# Shield_behuizing.net
KiCad netlist of a schematic drawn in EAGLE
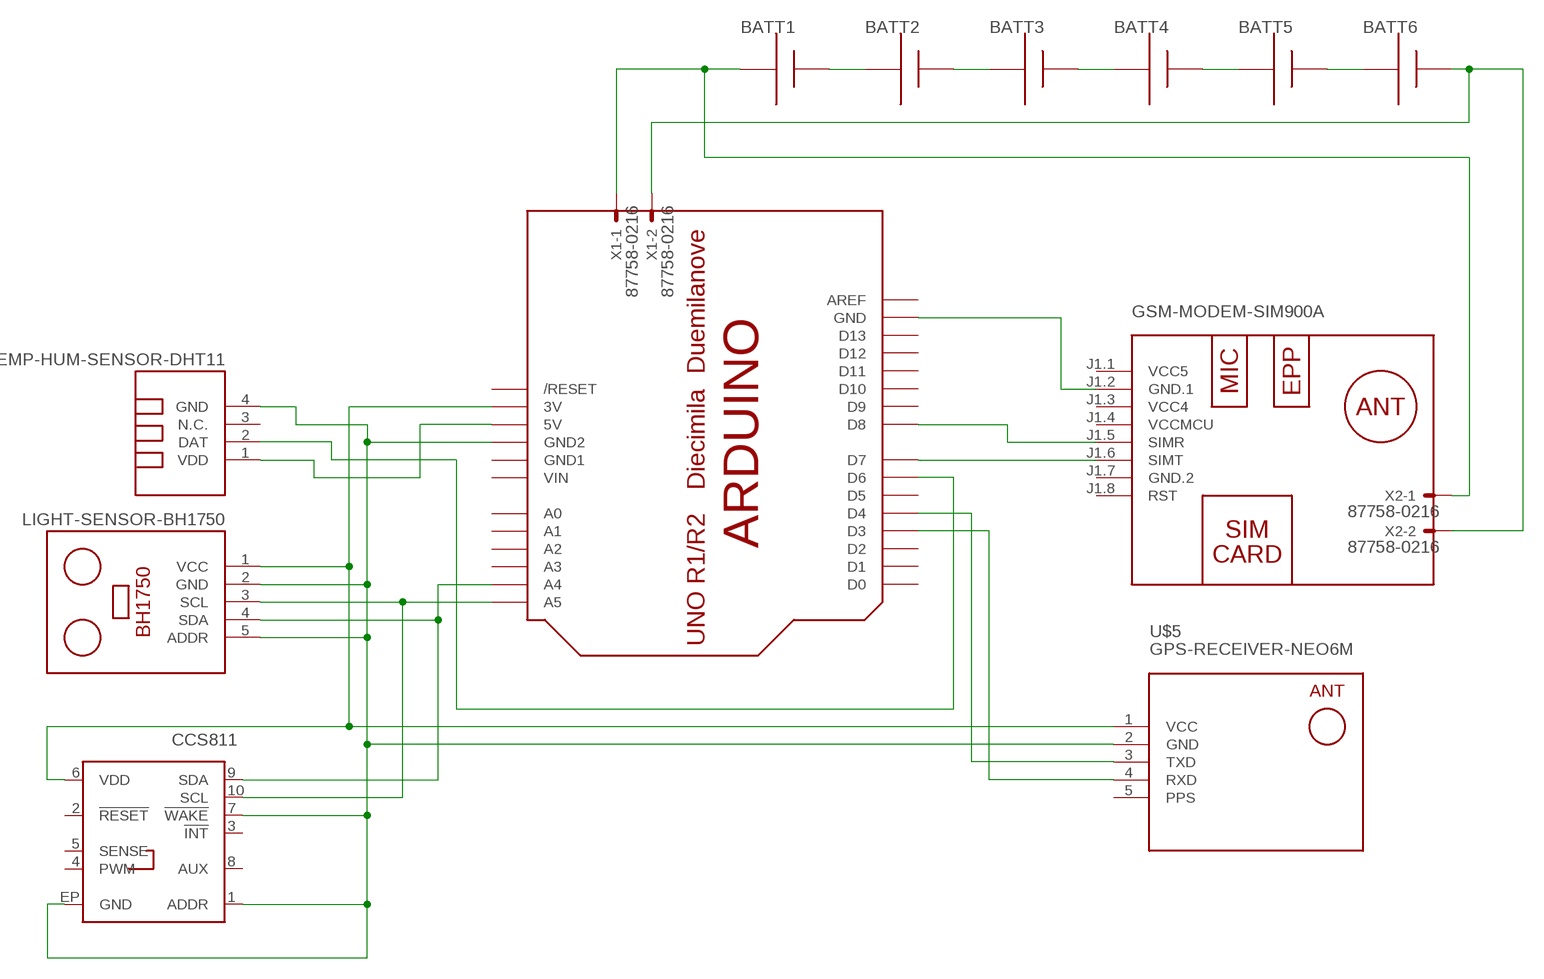
[diagram p0: schematic, sheet 1]

(export (version "E")
  (design (tool "Eeschema 10.0.6"))
  (components
    (comp (ref "BATT1")
      (value "AAA")
      (footprint "eagle-import:12BH412")
      (libsource (lib "eagle-import") (part "AAA"))
    )
    (comp (ref "BATT2")
      (value "AAA")
      (footprint "eagle-import:12BH412")
      (libsource (lib "eagle-import") (part "AAA"))
    )
    (comp (ref "BATT3")
      (value "AAA")
      (footprint "eagle-import:12BH412")
      (libsource (lib "eagle-import") (part "AAA"))
    )
    (comp (ref "BATT4")
      (value "AAA")
      (footprint "eagle-import:12BH412")
      (libsource (lib "eagle-import") (part "AAA"))
    )
    (comp (ref "BATT5")
      (value "AAA")
      (footprint "eagle-import:12BH412")
      (libsource (lib "eagle-import") (part "AAA"))
    )
    (comp (ref "BATT6")
      (value "AAA")
      (footprint "eagle-import:12BH412")
      (libsource (lib "eagle-import") (part "AAA"))
    )
    (comp (ref "U$1")
      (value "GSM-MODEM-SIM900A")
      (footprint "eagle-import:GSM-MODEM-SIM900A")
      (libsource (lib "eagle-import") (part "GSM-MODEM-SIM900A"))
    )
    (comp (ref "U$2")
      (value "ARDUINO-BPLACE")
      (footprint "eagle-import:ARDUINO-BPLACE")
      (libsource (lib "eagle-import") (part "ARDUINO-BPLACE"))
    )
    (comp (ref "U$3")
      (value "TEMP-HUM-SENSOR-DHT11")
      (footprint "eagle-import:TEMP-HUM-SENSOR-DHT11")
      (libsource (lib "eagle-import") (part "TEMP-HUM-SENSOR-DHT11"))
    )
    (comp (ref "U$4")
      (value "LIGHT-SENSOR-BH1750")
      (footprint "eagle-import:LIGHT-SENSOR-BH1750")
      (libsource (lib "eagle-import") (part "LIGHT-SENSOR-BH1750"))
    )
    (comp (ref "U$5")
      (value "GPS-RECEIVER-NEO6M")
      (footprint "eagle-import:GPS-RECEIVER-NEO6M")
      (libsource (lib "eagle-import") (part "GPS-RECEIVER-NEO6M"))
    )
    (comp (ref "U1")
      (value "CCS811")
      (footprint "eagle-import:LGA10")
      (libsource (lib "eagle-import") (part "CCS811"))
    )
    (comp (ref "X1")
      (value "87758-0216")
      (footprint "eagle-import:87758-0216")
      (fields (field (name "MF") "MOLEX"))
      (libsource (lib "eagle-import") (part "87758-0216"))
    )
    (comp (ref "X2")
      (value "87758-0216")
      (footprint "eagle-import:87758-0216")
      (fields (field (name "MF") "MOLEX"))
      (libsource (lib "eagle-import") (part "87758-0216"))
    )
  )
  (nets
    (net (code "1") (name "/GND.2") (class "Default")
      (node (ref "U$1") (pin "J1.7") (pinfunction "GND.2_J1.7") (pintype "power_in"))
    )
    (net (code "2") (name "/GND1") (class "Default")
      (node (ref "U$2") (pin "GND1") (pinfunction "GND1_GND1") (pintype "power_in"))
    )
    (net (code "3") (name "/PPS") (class "Default")
      (node (ref "U$5") (pin "5") (pinfunction "PPS_5") (pintype "power_in"))
    )
    (net (code "4") (name "/VCC4") (class "Default")
      (node (ref "U$1") (pin "J1.3") (pinfunction "VCC4_J1.3") (pintype "power_in"))
    )
    (net (code "5") (name "/VCC5") (class "Default")
      (node (ref "U$1") (pin "J1.1") (pinfunction "VCC5_J1.1") (pintype "power_in"))
    )
    (net (code "6") (name "/VCCMCU") (class "Default")
      (node (ref "U$1") (pin "J1.4") (pinfunction "VCCMCU_J1.4") (pintype "power_in"))
    )
    (net (code "7") (name "/VIN") (class "Default")
      (node (ref "U$2") (pin "VIN") (pinfunction "VIN_VIN") (pintype "power_in"))
    )
    (net (code "8") (name "Net-(BATT1-Pad+)") (class "Default")
      (node (ref "BATT1") (pin "+") (pinfunction "+_+") (pintype "bidirectional"))
      (node (ref "BATT2") (pin "-") (pinfunction "-_-") (pintype "bidirectional"))
    )
    (net (code "9") (name "Net-(BATT2-Pad+)") (class "Default")
      (node (ref "BATT2") (pin "+") (pinfunction "+_+") (pintype "bidirectional"))
      (node (ref "BATT3") (pin "-") (pinfunction "-_-") (pintype "bidirectional"))
    )
    (net (code "10") (name "Net-(BATT3-Pad+)") (class "Default")
      (node (ref "BATT3") (pin "+") (pinfunction "+_+") (pintype "bidirectional"))
      (node (ref "BATT4") (pin "-") (pinfunction "-_-") (pintype "bidirectional"))
    )
    (net (code "11") (name "Net-(BATT4-Pad+)") (class "Default")
      (node (ref "BATT4") (pin "+") (pinfunction "+_+") (pintype "bidirectional"))
      (node (ref "BATT5") (pin "-") (pinfunction "-_-") (pintype "bidirectional"))
    )
    (net (code "12") (name "Net-(BATT5-Pad+)") (class "Default")
      (node (ref "BATT5") (pin "+") (pinfunction "+_+") (pintype "bidirectional"))
      (node (ref "BATT6") (pin "-") (pinfunction "-_-") (pintype "bidirectional"))
    )
    (net (code "13") (name "Net-(U$1-GND.1)") (class "Default")
      (node (ref "U$1") (pin "J1.2") (pinfunction "GND.1_J1.2") (pintype "power_in"))
      (node (ref "U$2") (pin "GND") (pinfunction "GND_GND") (pintype "power_in"))
    )
    (net (code "14") (name "Net-(U$1-SIMR)") (class "Default")
      (node (ref "U$1") (pin "J1.5") (pinfunction "SIMR_J1.5") (pintype "bidirectional"))
      (node (ref "U$2") (pin "D8") (pinfunction "D8_D8") (pintype "bidirectional"))
    )
    (net (code "15") (name "Net-(U$1-SIMT)") (class "Default")
      (node (ref "U$1") (pin "J1.6") (pinfunction "SIMT_J1.6") (pintype "bidirectional"))
      (node (ref "U$2") (pin "D7") (pinfunction "D7_D7") (pintype "bidirectional"))
    )
    (net (code "16") (name "Net-(U$3-DAT)") (class "Default")
      (node (ref "U$2") (pin "D6") (pinfunction "D6_D6") (pintype "bidirectional"))
      (node (ref "U$3") (pin "2") (pinfunction "DAT_2") (pintype "bidirectional"))
    )
    (net (code "17") (name "Net-(U$3-GND)") (class "Default")
      (node (ref "U$2") (pin "GND2") (pinfunction "GND2_GND2") (pintype "power_in"))
      (node (ref "U$3") (pin "4") (pinfunction "GND_4") (pintype "power_in"))
      (node (ref "U$4") (pin "2") (pinfunction "GND_2") (pintype "power_in"))
      (node (ref "U$4") (pin "5") (pinfunction "ADDR_5") (pintype "bidirectional"))
      (node (ref "U$5") (pin "2") (pinfunction "GND_2") (pintype "bidirectional"))
      (node (ref "U1") (pin "1") (pinfunction "ADDR_1") (pintype "bidirectional"))
      (node (ref "U1") (pin "7") (pinfunction "~{WAKE}_7") (pintype "bidirectional"))
      (node (ref "U1") (pin "EP") (pinfunction "GND_EP") (pintype "bidirectional"))
    )
    (net (code "18") (name "Net-(U$3-VDD)") (class "Default")
      (node (ref "U$2") (pin "5V") (pinfunction "5V_5V") (pintype "power_in"))
      (node (ref "U$3") (pin "1") (pinfunction "VDD_1") (pintype "power_in"))
    )
    (net (code "19") (name "Net-(U$4-SCL)") (class "Default")
      (node (ref "U$2") (pin "A5") (pinfunction "A5_A5") (pintype "bidirectional"))
      (node (ref "U$4") (pin "3") (pinfunction "SCL_3") (pintype "bidirectional"))
      (node (ref "U1") (pin "10") (pinfunction "SCL_10") (pintype "bidirectional"))
    )
    (net (code "20") (name "Net-(U$4-SDA)") (class "Default")
      (node (ref "U$2") (pin "A4") (pinfunction "A4_A4") (pintype "bidirectional"))
      (node (ref "U$4") (pin "4") (pinfunction "SDA_4") (pintype "bidirectional"))
      (node (ref "U1") (pin "9") (pinfunction "SDA_9") (pintype "bidirectional"))
    )
    (net (code "21") (name "Net-(U$4-VCC)") (class "Default")
      (node (ref "U$2") (pin "3V") (pinfunction "3V_3V") (pintype "power_in"))
      (node (ref "U$4") (pin "1") (pinfunction "VCC_1") (pintype "power_in"))
      (node (ref "U$5") (pin "1") (pinfunction "VCC_1") (pintype "bidirectional"))
      (node (ref "U1") (pin "6") (pinfunction "VDD_6") (pintype "bidirectional"))
    )
    (net (code "22") (name "Net-(U$5-RXD)") (class "Default")
      (node (ref "U$2") (pin "D3") (pinfunction "D3_D3") (pintype "bidirectional"))
      (node (ref "U$5") (pin "4") (pinfunction "RXD_4") (pintype "power_in"))
    )
    (net (code "23") (name "Net-(U$5-TXD)") (class "Default")
      (node (ref "U$2") (pin "D4") (pinfunction "D4_D4") (pintype "bidirectional"))
      (node (ref "U$5") (pin "3") (pinfunction "TXD_3") (pintype "bidirectional"))
    )
    (net (code "24") (name "Net-(X1A-S)") (class "Default")
      (node (ref "BATT1") (pin "-") (pinfunction "-_-") (pintype "bidirectional"))
      (node (ref "X1") (pin "1") (pinfunction "S_1") (pintype "passive"))
      (node (ref "X2") (pin "1") (pinfunction "S_1") (pintype "passive"))
    )
    (net (code "25") (name "Net-(X1B-S)") (class "Default")
      (node (ref "BATT6") (pin "+") (pinfunction "+_+") (pintype "bidirectional"))
      (node (ref "X1") (pin "2") (pinfunction "S_2") (pintype "passive"))
      (node (ref "X2") (pin "2") (pinfunction "S_2") (pintype "passive"))
    )
    (net (code "26") (name "unconnected-(U$1-RST-PadJ1.8)") (class "Default")
      (node (ref "U$1") (pin "J1.8") (pinfunction "RST_J1.8") (pintype "bidirectional"))
    )
    (net (code "27") (name "unconnected-(U$2-PadA0)") (class "Default")
      (node (ref "U$2") (pin "A0") (pinfunction "A0_A0") (pintype "bidirectional"))
    )
    (net (code "28") (name "unconnected-(U$2-PadA1)") (class "Default")
      (node (ref "U$2") (pin "A1") (pinfunction "A1_A1") (pintype "bidirectional"))
    )
    (net (code "29") (name "unconnected-(U$2-PadA2)") (class "Default")
      (node (ref "U$2") (pin "A2") (pinfunction "A2_A2") (pintype "bidirectional"))
    )
    (net (code "30") (name "unconnected-(U$2-PadA3)") (class "Default")
      (node (ref "U$2") (pin "A3") (pinfunction "A3_A3") (pintype "bidirectional"))
    )
    (net (code "31") (name "unconnected-(U$2-PadAREF)") (class "Default")
      (node (ref "U$2") (pin "AREF") (pinfunction "AREF_AREF") (pintype "bidirectional"))
    )
    (net (code "32") (name "unconnected-(U$2-PadD0)") (class "Default")
      (node (ref "U$2") (pin "D0") (pinfunction "D0_D0") (pintype "bidirectional"))
    )
    (net (code "33") (name "unconnected-(U$2-PadD1)") (class "Default")
      (node (ref "U$2") (pin "D1") (pinfunction "D1_D1") (pintype "bidirectional"))
    )
    (net (code "34") (name "unconnected-(U$2-PadD2)") (class "Default")
      (node (ref "U$2") (pin "D2") (pinfunction "D2_D2") (pintype "bidirectional"))
    )
    (net (code "35") (name "unconnected-(U$2-PadD5)") (class "Default")
      (node (ref "U$2") (pin "D5") (pinfunction "D5_D5") (pintype "bidirectional"))
    )
    (net (code "36") (name "unconnected-(U$2-PadD9)") (class "Default")
      (node (ref "U$2") (pin "D9") (pinfunction "D9_D9") (pintype "bidirectional"))
    )
    (net (code "37") (name "unconnected-(U$2-PadD10)") (class "Default")
      (node (ref "U$2") (pin "D10") (pinfunction "D10_D10") (pintype "bidirectional"))
    )
    (net (code "38") (name "unconnected-(U$2-PadD11)") (class "Default")
      (node (ref "U$2") (pin "D11") (pinfunction "D11_D11") (pintype "bidirectional"))
    )
    (net (code "39") (name "unconnected-(U$2-PadD12)") (class "Default")
      (node (ref "U$2") (pin "D12") (pinfunction "D12_D12") (pintype "bidirectional"))
    )
    (net (code "40") (name "unconnected-(U$2-PadD13)") (class "Default")
      (node (ref "U$2") (pin "D13") (pinfunction "D13_D13") (pintype "bidirectional"))
    )
    (net (code "41") (name "unconnected-(U$2-{slash}RESET-PadRESET)") (class "Default")
      (node (ref "U$2") (pin "RESET") (pinfunction "/RESET_RESET") (pintype "bidirectional"))
    )
    (net (code "42") (name "unconnected-(U$3-N.C.-Pad3)") (class "Default")
      (node (ref "U$3") (pin "3") (pinfunction "N.C._3") (pintype "passive"))
    )
    (net (code "43") (name "unconnected-(U1-AUX-Pad8)") (class "Default")
      (node (ref "U1") (pin "8") (pinfunction "AUX_8") (pintype "bidirectional"))
    )
    (net (code "44") (name "unconnected-(U1-PWM-Pad4)") (class "Default")
      (node (ref "U1") (pin "4") (pinfunction "PWM_4") (pintype "bidirectional"))
    )
    (net (code "45") (name "unconnected-(U1-SENSE-Pad5)") (class "Default")
      (node (ref "U1") (pin "5") (pinfunction "SENSE_5") (pintype "bidirectional"))
    )
    (net (code "46") (name "unconnected-(U1-~{INT}-Pad3)") (class "Default")
      (node (ref "U1") (pin "3") (pinfunction "~{INT}_3") (pintype "bidirectional"))
    )
    (net (code "47") (name "unconnected-(U1-~{RESET}-Pad2)") (class "Default")
      (node (ref "U1") (pin "2") (pinfunction "~{RESET}_2") (pintype "bidirectional"))
    )
  )
)
